# ESP32_S2_solo.net
KiCad netlist of a schematic drawn in Altium Designer
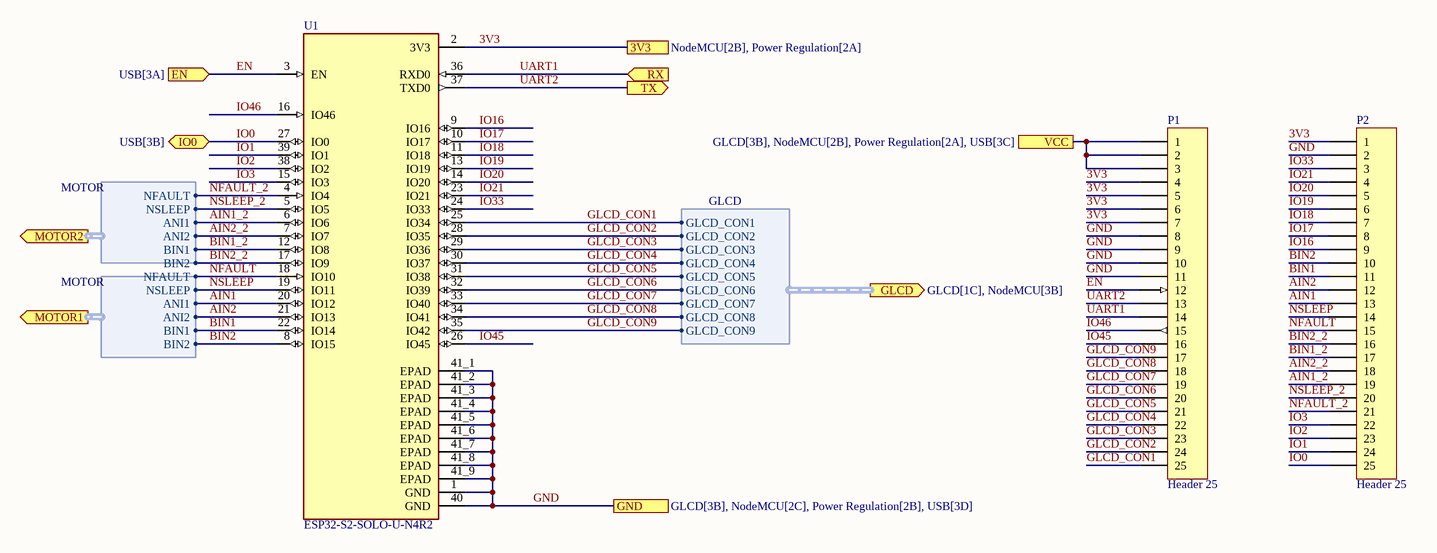
[diagram p0: ESP32_S2_solo.SchDoc]

(export (version "E")
  (design (tool "Eeschema 10.0.6"))
  (components
    (comp (ref "P1")
      (value "Header 25")
      (footprint "HDR1X25")
      (description "Header, 25-Pin")
      (fields (field (name "PUBLISHER") "Altium Limited"))
      (libsource (lib "Miscellaneous Connectors") (part "Header 25"))
    )
    (comp (ref "P2")
      (value "Header 25")
      (footprint "HDR1X25")
      (description "Header, 25-Pin")
      (fields (field (name "PUBLISHER") "Altium Limited"))
      (libsource (lib "Miscellaneous Connectors") (part "Header 25"))
    )
    (comp (ref "U1")
      (value "ESP32-S2-SOLO-U-N4R2")
      (footprint "XCVR_ESP32-S2-SOLO-U-N4R2")
      (fields (field (name "MF") "{'manufacturer': u'Espressif Systems'}"))
      (libsource (lib "SnapEDA_Library") (part "ESP32-S2-SOLO-U-N4R2"))
    )
  )
  (nets
    (net (code "3") (name "/3V3") (class "Default")
      (node (ref "P1") (pin "4") (pinfunction "4_4") (pintype "passive"))
      (node (ref "P1") (pin "5") (pinfunction "5_5") (pintype "passive"))
      (node (ref "P1") (pin "6") (pinfunction "6_6") (pintype "passive"))
      (node (ref "P1") (pin "7") (pinfunction "7_7") (pintype "passive"))
      (node (ref "P2") (pin "1") (pinfunction "1_1") (pintype "passive"))
      (node (ref "U1") (pin "2") (pinfunction "3V3_2") (pintype "power_in"))
    )
    (net (code "4") (name "/AIN1") (class "Default")
      (node (ref "P2") (pin "13") (pinfunction "13_13") (pintype "passive"))
      (node (ref "U1") (pin "20") (pinfunction "IO12_20") (pintype "bidirectional"))
    )
    (net (code "5") (name "/AIN1_2") (class "Default")
      (node (ref "P2") (pin "19") (pinfunction "19_19") (pintype "passive"))
      (node (ref "U1") (pin "6") (pinfunction "IO6_6") (pintype "bidirectional"))
    )
    (net (code "6") (name "/AIN2") (class "Default")
      (node (ref "P2") (pin "12") (pinfunction "12_12") (pintype "input"))
      (node (ref "U1") (pin "21") (pinfunction "IO13_21") (pintype "bidirectional"))
    )
    (net (code "7") (name "/AIN2_2") (class "Default")
      (node (ref "P2") (pin "18") (pinfunction "18_18") (pintype "passive"))
      (node (ref "U1") (pin "7") (pinfunction "IO7_7") (pintype "bidirectional"))
    )
    (net (code "8") (name "/BIN1") (class "Default")
      (node (ref "P2") (pin "11") (pinfunction "11_11") (pintype "passive"))
      (node (ref "U1") (pin "22") (pinfunction "IO14_22") (pintype "bidirectional"))
    )
    (net (code "9") (name "/BIN1_2") (class "Default")
      (node (ref "P2") (pin "17") (pinfunction "17_17") (pintype "passive"))
      (node (ref "U1") (pin "12") (pinfunction "IO8_12") (pintype "bidirectional"))
    )
    (net (code "10") (name "/BIN2") (class "Default")
      (node (ref "P2") (pin "10") (pinfunction "10_10") (pintype "passive"))
      (node (ref "U1") (pin "8") (pinfunction "IO15_8") (pintype "bidirectional"))
    )
    (net (code "11") (name "/BIN2_2") (class "Default")
      (node (ref "P2") (pin "16") (pinfunction "16_16") (pintype "passive"))
      (node (ref "U1") (pin "17") (pinfunction "IO9_17") (pintype "bidirectional"))
    )
    (net (code "12") (name "/EN") (class "Default")
      (node (ref "P1") (pin "12") (pinfunction "12_12") (pintype "input"))
      (node (ref "U1") (pin "3") (pinfunction "EN_3") (pintype "input"))
    )
    (net (code "13") (name "/GLCD_CON1") (class "Default")
      (node (ref "P1") (pin "25") (pinfunction "25_25") (pintype "passive"))
      (node (ref "U1") (pin "25") (pinfunction "IO34_25") (pintype "bidirectional"))
    )
    (net (code "14") (name "/GLCD_CON2") (class "Default")
      (node (ref "P1") (pin "24") (pinfunction "24_24") (pintype "passive"))
      (node (ref "U1") (pin "28") (pinfunction "IO35_28") (pintype "bidirectional"))
    )
    (net (code "15") (name "/GLCD_CON3") (class "Default")
      (node (ref "P1") (pin "23") (pinfunction "23_23") (pintype "passive"))
      (node (ref "U1") (pin "29") (pinfunction "IO36_29") (pintype "bidirectional"))
    )
    (net (code "16") (name "/GLCD_CON4") (class "Default")
      (node (ref "P1") (pin "22") (pinfunction "22_22") (pintype "passive"))
      (node (ref "U1") (pin "30") (pinfunction "IO37_30") (pintype "bidirectional"))
    )
    (net (code "17") (name "/GLCD_CON5") (class "Default")
      (node (ref "P1") (pin "21") (pinfunction "21_21") (pintype "passive"))
      (node (ref "U1") (pin "31") (pinfunction "IO38_31") (pintype "bidirectional"))
    )
    (net (code "18") (name "/GLCD_CON6") (class "Default")
      (node (ref "P1") (pin "20") (pinfunction "20_20") (pintype "passive"))
      (node (ref "U1") (pin "32") (pinfunction "IO39_32") (pintype "bidirectional"))
    )
    (net (code "19") (name "/GLCD_CON7") (class "Default")
      (node (ref "P1") (pin "19") (pinfunction "19_19") (pintype "passive"))
      (node (ref "U1") (pin "33") (pinfunction "IO40_33") (pintype "bidirectional"))
    )
    (net (code "20") (name "/GLCD_CON8") (class "Default")
      (node (ref "P1") (pin "18") (pinfunction "18_18") (pintype "passive"))
      (node (ref "U1") (pin "34") (pinfunction "IO41_34") (pintype "bidirectional"))
    )
    (net (code "21") (name "/GLCD_CON9") (class "Default")
      (node (ref "P1") (pin "17") (pinfunction "17_17") (pintype "passive"))
      (node (ref "U1") (pin "35") (pinfunction "IO42_35") (pintype "bidirectional"))
    )
    (net (code "22") (name "/GND") (class "Default")
      (node (ref "P1") (pin "10") (pinfunction "10_10") (pintype "passive"))
      (node (ref "P1") (pin "11") (pinfunction "11_11") (pintype "passive"))
      (node (ref "P1") (pin "8") (pinfunction "8_8") (pintype "passive"))
      (node (ref "P1") (pin "9") (pinfunction "9_9") (pintype "passive"))
      (node (ref "P2") (pin "2") (pinfunction "2_2") (pintype "passive"))
      (node (ref "U1") (pin "1") (pinfunction "GND_1") (pintype "power_in"))
      (node (ref "U1") (pin "40") (pinfunction "GND_40") (pintype "power_in"))
      (node (ref "U1") (pin "41_1") (pinfunction "EPAD_41_1") (pintype "power_in"))
      (node (ref "U1") (pin "41_2") (pinfunction "EPAD_41_2") (pintype "power_in"))
      (node (ref "U1") (pin "41_3") (pinfunction "EPAD_41_3") (pintype "power_in"))
      (node (ref "U1") (pin "41_4") (pinfunction "EPAD_41_4") (pintype "power_in"))
      (node (ref "U1") (pin "41_5") (pinfunction "EPAD_41_5") (pintype "power_in"))
      (node (ref "U1") (pin "41_6") (pinfunction "EPAD_41_6") (pintype "power_in"))
      (node (ref "U1") (pin "41_7") (pinfunction "EPAD_41_7") (pintype "power_in"))
      (node (ref "U1") (pin "41_8") (pinfunction "EPAD_41_8") (pintype "power_in"))
      (node (ref "U1") (pin "41_9") (pinfunction "EPAD_41_9") (pintype "power_in"))
    )
    (net (code "23") (name "/IO0") (class "Default")
      (node (ref "P2") (pin "25") (pinfunction "25_25") (pintype "passive"))
      (node (ref "U1") (pin "27") (pinfunction "IO0_27") (pintype "bidirectional"))
    )
    (net (code "24") (name "/IO1") (class "Default")
      (node (ref "P2") (pin "24") (pinfunction "24_24") (pintype "passive"))
      (node (ref "U1") (pin "39") (pinfunction "IO1_39") (pintype "bidirectional"))
    )
    (net (code "25") (name "/IO2") (class "Default")
      (node (ref "P2") (pin "23") (pinfunction "23_23") (pintype "passive"))
      (node (ref "U1") (pin "38") (pinfunction "IO2_38") (pintype "bidirectional"))
    )
    (net (code "26") (name "/IO3") (class "Default")
      (node (ref "P2") (pin "22") (pinfunction "22_22") (pintype "passive"))
      (node (ref "U1") (pin "15") (pinfunction "IO3_15") (pintype "bidirectional"))
    )
    (net (code "27") (name "/IO16") (class "Default")
      (node (ref "P2") (pin "9") (pinfunction "9_9") (pintype "passive"))
      (node (ref "U1") (pin "9") (pinfunction "IO16_9") (pintype "bidirectional"))
    )
    (net (code "28") (name "/IO17") (class "Default")
      (node (ref "P2") (pin "8") (pinfunction "8_8") (pintype "passive"))
      (node (ref "U1") (pin "10") (pinfunction "IO17_10") (pintype "bidirectional"))
    )
    (net (code "29") (name "/IO18") (class "Default")
      (node (ref "P2") (pin "7") (pinfunction "7_7") (pintype "passive"))
      (node (ref "U1") (pin "11") (pinfunction "IO18_11") (pintype "bidirectional"))
    )
    (net (code "30") (name "/IO19") (class "Default")
      (node (ref "P2") (pin "6") (pinfunction "6_6") (pintype "passive"))
      (node (ref "U1") (pin "13") (pinfunction "IO19_13") (pintype "bidirectional"))
    )
    (net (code "31") (name "/IO20") (class "Default")
      (node (ref "P2") (pin "5") (pinfunction "5_5") (pintype "passive"))
      (node (ref "U1") (pin "14") (pinfunction "IO20_14") (pintype "bidirectional"))
    )
    (net (code "32") (name "/IO21") (class "Default")
      (node (ref "P2") (pin "4") (pinfunction "4_4") (pintype "passive"))
      (node (ref "U1") (pin "23") (pinfunction "IO21_23") (pintype "bidirectional"))
    )
    (net (code "33") (name "/IO33") (class "Default")
      (node (ref "P2") (pin "3") (pinfunction "3_3") (pintype "passive"))
      (node (ref "U1") (pin "24") (pinfunction "IO33_24") (pintype "bidirectional"))
    )
    (net (code "34") (name "/IO45") (class "Default")
      (node (ref "P1") (pin "16") (pinfunction "16_16") (pintype "passive"))
      (node (ref "U1") (pin "26") (pinfunction "IO45_26") (pintype "bidirectional"))
    )
    (net (code "35") (name "/IO46") (class "Default")
      (node (ref "P1") (pin "15") (pinfunction "15_15") (pintype "output"))
      (node (ref "U1") (pin "16") (pinfunction "IO46_16") (pintype "input"))
    )
    (net (code "36") (name "/NFAULT") (class "Default")
      (node (ref "P2") (pin "15") (pinfunction "15_15") (pintype "output"))
      (node (ref "U1") (pin "18") (pinfunction "IO10_18") (pintype "input"))
    )
    (net (code "37") (name "/NFAULT_2") (class "Default")
      (node (ref "P2") (pin "21") (pinfunction "21_21") (pintype "passive"))
      (node (ref "U1") (pin "4") (pinfunction "IO4_4") (pintype "input"))
    )
    (net (code "38") (name "/NSLEEP") (class "Default")
      (node (ref "P2") (pin "14") (pinfunction "14_14") (pintype "passive"))
      (node (ref "U1") (pin "19") (pinfunction "IO11_19") (pintype "bidirectional"))
    )
    (net (code "39") (name "/NSLEEP_2") (class "Default")
      (node (ref "P2") (pin "20") (pinfunction "20_20") (pintype "passive"))
      (node (ref "U1") (pin "5") (pinfunction "IO5_5") (pintype "bidirectional"))
    )
    (net (code "40") (name "/UART1") (class "Default")
      (node (ref "P1") (pin "14") (pinfunction "14_14") (pintype "passive"))
      (node (ref "U1") (pin "36") (pinfunction "RXD0_36") (pintype "input"))
    )
    (net (code "41") (name "/UART2") (class "Default")
      (node (ref "P1") (pin "13") (pinfunction "13_13") (pintype "passive"))
      (node (ref "U1") (pin "37") (pinfunction "TXD0_37") (pintype "output"))
    )
    (net (code "42") (name "/VCC") (class "Default")
      (node (ref "P1") (pin "1") (pinfunction "1_1") (pintype "passive"))
      (node (ref "P1") (pin "2") (pinfunction "2_2") (pintype "passive"))
      (node (ref "P1") (pin "3") (pinfunction "3_3") (pintype "passive"))
    )
  )
)
